# lcd.net
KiCad netlist of a schematic drawn in EAGLE
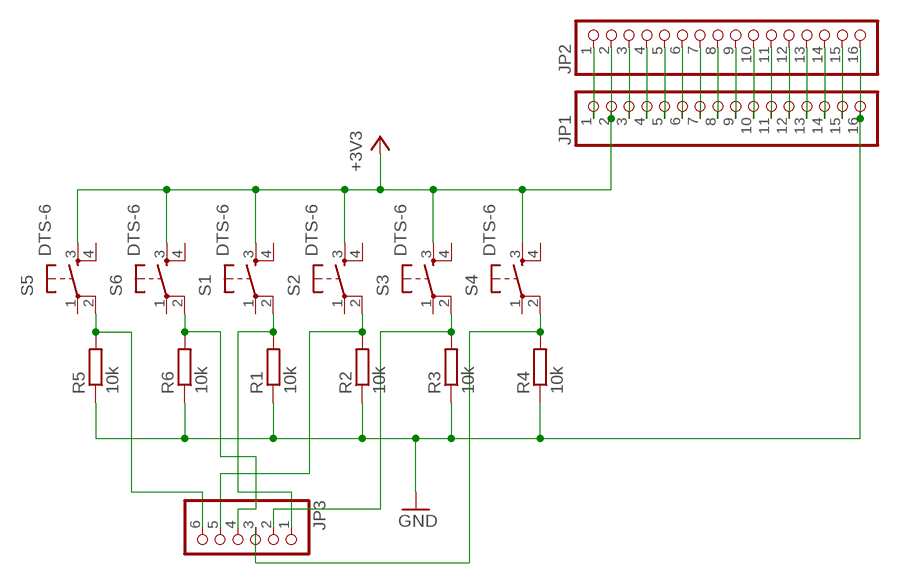
[diagram p0: schematic, sheet 1]

(export (version "E")
  (design (tool "Eeschema 10.0.6"))
  (components
    (comp (ref "JP1")
      (value "PINHD-1X16")
      (footprint "eagle-import:1X16")
      (libsource (lib "eagle-import") (part "PINHD-1X16"))
    )
    (comp (ref "JP2")
      (value "PINHD-1X16")
      (footprint "eagle-import:1X16")
      (libsource (lib "eagle-import") (part "PINHD-1X16"))
    )
    (comp (ref "JP3")
      (value "PINHD-1X6")
      (footprint "eagle-import:1X06")
      (libsource (lib "eagle-import") (part "PINHD-1X6"))
    )
    (comp (ref "R1")
      (value "10k")
      (footprint "eagle-import:R0805")
      (libsource (lib "eagle-import") (part "R-EU_R0805"))
    )
    (comp (ref "R2")
      (value "10k")
      (footprint "eagle-import:R0805")
      (libsource (lib "eagle-import") (part "R-EU_R0805"))
    )
    (comp (ref "R3")
      (value "10k")
      (footprint "eagle-import:R0805")
      (libsource (lib "eagle-import") (part "R-EU_R0805"))
    )
    (comp (ref "R4")
      (value "10k")
      (footprint "eagle-import:R0805")
      (libsource (lib "eagle-import") (part "R-EU_R0805"))
    )
    (comp (ref "R5")
      (value "10k")
      (footprint "eagle-import:R0805")
      (libsource (lib "eagle-import") (part "R-EU_R0805"))
    )
    (comp (ref "R6")
      (value "10k")
      (footprint "eagle-import:R0805")
      (libsource (lib "eagle-import") (part "R-EU_R0805"))
    )
    (comp (ref "S1")
      (value "DTS-6")
      (footprint "eagle-import:DTS-6")
      (libsource (lib "eagle-import") (part "DTS-6"))
    )
    (comp (ref "S2")
      (value "DTS-6")
      (footprint "eagle-import:DTS-6")
      (libsource (lib "eagle-import") (part "DTS-6"))
    )
    (comp (ref "S3")
      (value "DTS-6")
      (footprint "eagle-import:DTS-6")
      (libsource (lib "eagle-import") (part "DTS-6"))
    )
    (comp (ref "S4")
      (value "DTS-6")
      (footprint "eagle-import:DTS-6")
      (libsource (lib "eagle-import") (part "DTS-6"))
    )
    (comp (ref "S5")
      (value "DTS-6")
      (footprint "eagle-import:DTS-6")
      (libsource (lib "eagle-import") (part "DTS-6"))
    )
    (comp (ref "S6")
      (value "DTS-6")
      (footprint "eagle-import:DTS-6")
      (libsource (lib "eagle-import") (part "DTS-6"))
    )
  )
  (nets
    (net (code "1") (name "+3V3") (class "Default")
      (node (ref "JP1") (pin "2") (pinfunction "2_2") (pintype "passive"))
      (node (ref "JP2") (pin "2") (pinfunction "2_2") (pintype "passive"))
      (node (ref "S1") (pin "3") (pinfunction "3_3") (pintype "passive"))
      (node (ref "S2") (pin "3") (pinfunction "3_3") (pintype "passive"))
      (node (ref "S3") (pin "3") (pinfunction "3_3") (pintype "passive"))
      (node (ref "S4") (pin "3") (pinfunction "3_3") (pintype "passive"))
      (node (ref "S5") (pin "3") (pinfunction "3_3") (pintype "passive"))
      (node (ref "S6") (pin "3") (pinfunction "3_3") (pintype "passive"))
    )
    (net (code "2") (name "GND") (class "Default")
      (node (ref "JP1") (pin "16") (pinfunction "16_16") (pintype "passive"))
      (node (ref "JP2") (pin "16") (pinfunction "16_16") (pintype "passive"))
      (node (ref "R1") (pin "1") (pinfunction "1_1") (pintype "passive"))
      (node (ref "R2") (pin "1") (pinfunction "1_1") (pintype "passive"))
      (node (ref "R3") (pin "1") (pinfunction "1_1") (pintype "passive"))
      (node (ref "R4") (pin "1") (pinfunction "1_1") (pintype "passive"))
      (node (ref "R5") (pin "1") (pinfunction "1_1") (pintype "passive"))
      (node (ref "R6") (pin "1") (pinfunction "1_1") (pintype "passive"))
    )
    (net (code "3") (name "Net-(JP1-Pad1)") (class "Default")
      (node (ref "JP1") (pin "1") (pinfunction "1_1") (pintype "passive"))
      (node (ref "JP2") (pin "1") (pinfunction "1_1") (pintype "passive"))
    )
    (net (code "4") (name "Net-(JP1-Pad3)") (class "Default")
      (node (ref "JP1") (pin "3") (pinfunction "3_3") (pintype "passive"))
      (node (ref "JP2") (pin "3") (pinfunction "3_3") (pintype "passive"))
    )
    (net (code "5") (name "Net-(JP1-Pad4)") (class "Default")
      (node (ref "JP1") (pin "4") (pinfunction "4_4") (pintype "passive"))
      (node (ref "JP2") (pin "4") (pinfunction "4_4") (pintype "passive"))
    )
    (net (code "6") (name "Net-(JP1-Pad5)") (class "Default")
      (node (ref "JP1") (pin "5") (pinfunction "5_5") (pintype "passive"))
      (node (ref "JP2") (pin "5") (pinfunction "5_5") (pintype "passive"))
    )
    (net (code "7") (name "Net-(JP1-Pad6)") (class "Default")
      (node (ref "JP1") (pin "6") (pinfunction "6_6") (pintype "passive"))
      (node (ref "JP2") (pin "6") (pinfunction "6_6") (pintype "passive"))
    )
    (net (code "8") (name "Net-(JP1-Pad7)") (class "Default")
      (node (ref "JP1") (pin "7") (pinfunction "7_7") (pintype "passive"))
      (node (ref "JP2") (pin "7") (pinfunction "7_7") (pintype "passive"))
    )
    (net (code "9") (name "Net-(JP1-Pad8)") (class "Default")
      (node (ref "JP1") (pin "8") (pinfunction "8_8") (pintype "passive"))
      (node (ref "JP2") (pin "8") (pinfunction "8_8") (pintype "passive"))
    )
    (net (code "10") (name "Net-(JP1-Pad9)") (class "Default")
      (node (ref "JP1") (pin "9") (pinfunction "9_9") (pintype "passive"))
      (node (ref "JP2") (pin "9") (pinfunction "9_9") (pintype "passive"))
    )
    (net (code "11") (name "Net-(JP1-Pad10)") (class "Default")
      (node (ref "JP1") (pin "10") (pinfunction "10_10") (pintype "passive"))
      (node (ref "JP2") (pin "10") (pinfunction "10_10") (pintype "passive"))
    )
    (net (code "12") (name "Net-(JP1-Pad11)") (class "Default")
      (node (ref "JP1") (pin "11") (pinfunction "11_11") (pintype "passive"))
      (node (ref "JP2") (pin "11") (pinfunction "11_11") (pintype "passive"))
    )
    (net (code "13") (name "Net-(JP1-Pad12)") (class "Default")
      (node (ref "JP1") (pin "12") (pinfunction "12_12") (pintype "passive"))
      (node (ref "JP2") (pin "12") (pinfunction "12_12") (pintype "passive"))
    )
    (net (code "14") (name "Net-(JP1-Pad13)") (class "Default")
      (node (ref "JP1") (pin "13") (pinfunction "13_13") (pintype "passive"))
      (node (ref "JP2") (pin "13") (pinfunction "13_13") (pintype "passive"))
    )
    (net (code "15") (name "Net-(JP1-Pad14)") (class "Default")
      (node (ref "JP1") (pin "14") (pinfunction "14_14") (pintype "passive"))
      (node (ref "JP2") (pin "14") (pinfunction "14_14") (pintype "passive"))
    )
    (net (code "16") (name "Net-(JP1-Pad15)") (class "Default")
      (node (ref "JP1") (pin "15") (pinfunction "15_15") (pintype "passive"))
      (node (ref "JP2") (pin "15") (pinfunction "15_15") (pintype "passive"))
    )
    (net (code "17") (name "Net-(JP3-Pad1)") (class "Default")
      (node (ref "JP3") (pin "1") (pinfunction "1_1") (pintype "passive"))
      (node (ref "R1") (pin "2") (pinfunction "2_2") (pintype "passive"))
      (node (ref "S1") (pin "2") (pinfunction "2_2") (pintype "passive"))
    )
    (net (code "18") (name "Net-(JP3-Pad2)") (class "Default")
      (node (ref "JP3") (pin "2") (pinfunction "2_2") (pintype "passive"))
      (node (ref "R3") (pin "2") (pinfunction "2_2") (pintype "passive"))
      (node (ref "S3") (pin "2") (pinfunction "2_2") (pintype "passive"))
    )
    (net (code "19") (name "Net-(JP3-Pad3)") (class "Default")
      (node (ref "JP3") (pin "3") (pinfunction "3_3") (pintype "passive"))
      (node (ref "R4") (pin "2") (pinfunction "2_2") (pintype "passive"))
      (node (ref "S4") (pin "2") (pinfunction "2_2") (pintype "passive"))
    )
    (net (code "20") (name "Net-(JP3-Pad4)") (class "Default")
      (node (ref "JP3") (pin "4") (pinfunction "4_4") (pintype "passive"))
      (node (ref "R6") (pin "2") (pinfunction "2_2") (pintype "passive"))
      (node (ref "S6") (pin "2") (pinfunction "2_2") (pintype "passive"))
    )
    (net (code "21") (name "Net-(JP3-Pad5)") (class "Default")
      (node (ref "JP3") (pin "5") (pinfunction "5_5") (pintype "passive"))
      (node (ref "R2") (pin "2") (pinfunction "2_2") (pintype "passive"))
      (node (ref "S2") (pin "2") (pinfunction "2_2") (pintype "passive"))
    )
    (net (code "22") (name "Net-(JP3-Pad6)") (class "Default")
      (node (ref "JP3") (pin "6") (pinfunction "6_6") (pintype "passive"))
      (node (ref "R5") (pin "2") (pinfunction "2_2") (pintype "passive"))
      (node (ref "S5") (pin "2") (pinfunction "2_2") (pintype "passive"))
    )
    (net (code "23") (name "unconnected-(S1-Pad1)") (class "Default")
      (node (ref "S1") (pin "1") (pinfunction "1_1") (pintype "passive"))
    )
    (net (code "24") (name "unconnected-(S1-Pad4)") (class "Default")
      (node (ref "S1") (pin "4") (pinfunction "4_4") (pintype "passive"))
    )
    (net (code "25") (name "unconnected-(S2-Pad1)") (class "Default")
      (node (ref "S2") (pin "1") (pinfunction "1_1") (pintype "passive"))
    )
    (net (code "26") (name "unconnected-(S2-Pad4)") (class "Default")
      (node (ref "S2") (pin "4") (pinfunction "4_4") (pintype "passive"))
    )
    (net (code "27") (name "unconnected-(S3-Pad1)") (class "Default")
      (node (ref "S3") (pin "1") (pinfunction "1_1") (pintype "passive"))
    )
    (net (code "28") (name "unconnected-(S3-Pad4)") (class "Default")
      (node (ref "S3") (pin "4") (pinfunction "4_4") (pintype "passive"))
    )
    (net (code "29") (name "unconnected-(S4-Pad1)") (class "Default")
      (node (ref "S4") (pin "1") (pinfunction "1_1") (pintype "passive"))
    )
    (net (code "30") (name "unconnected-(S4-Pad4)") (class "Default")
      (node (ref "S4") (pin "4") (pinfunction "4_4") (pintype "passive"))
    )
    (net (code "31") (name "unconnected-(S5-Pad1)") (class "Default")
      (node (ref "S5") (pin "1") (pinfunction "1_1") (pintype "passive"))
    )
    (net (code "32") (name "unconnected-(S5-Pad4)") (class "Default")
      (node (ref "S5") (pin "4") (pinfunction "4_4") (pintype "passive"))
    )
    (net (code "33") (name "unconnected-(S6-Pad1)") (class "Default")
      (node (ref "S6") (pin "1") (pinfunction "1_1") (pintype "passive"))
    )
    (net (code "34") (name "unconnected-(S6-Pad4)") (class "Default")
      (node (ref "S6") (pin "4") (pinfunction "4_4") (pintype "passive"))
    )
  )
)
